# STM32-RF.net
KiCad netlist of a schematic drawn in EAGLE
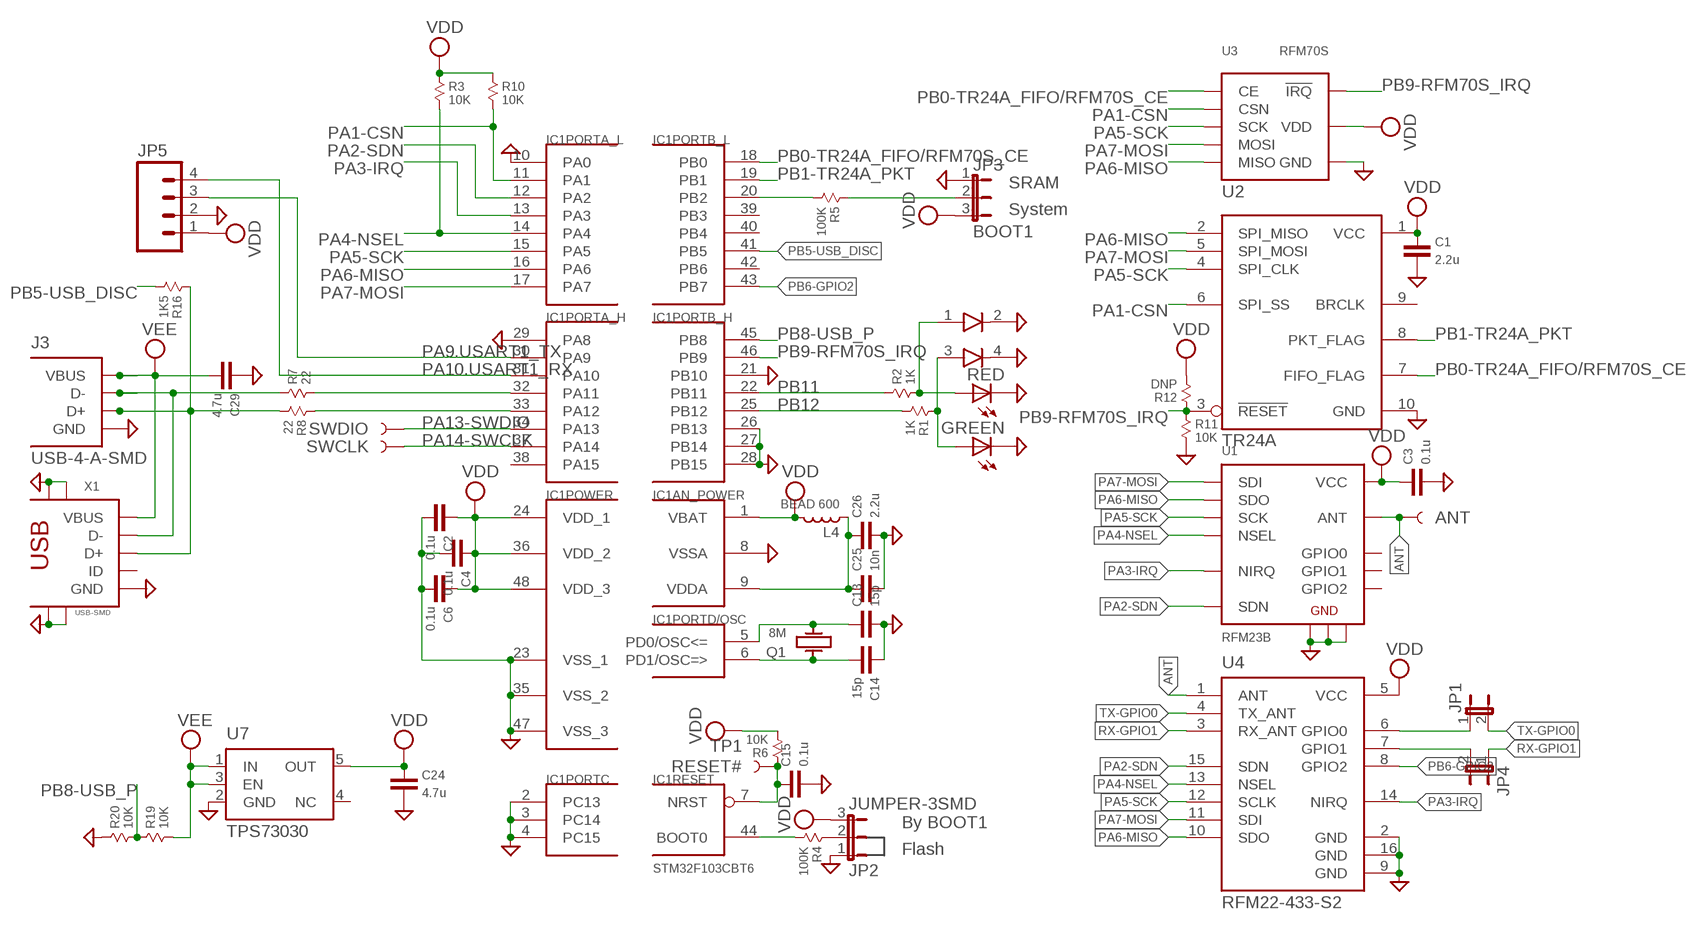
[diagram p0: schematic, sheet 1]

(export (version "E")
  (design (tool "Eeschema 10.0.6"))
  (components
    (comp (ref "ANT")
      (value "TEST-POINT1")
      (footprint "eagle-import:PAD.1X1")
      (libsource (lib "eagle-import") (part "TEST-POINT1"))
    )
    (comp (ref "C1")
      (value "2.2u")
      (footprint "eagle-import:0603")
      (libsource (lib "eagle-import") (part "CAP-0603"))
    )
    (comp (ref "C2")
      (value "0.1u")
      (footprint "eagle-import:0603")
      (libsource (lib "eagle-import") (part "CAP-0603"))
    )
    (comp (ref "C3")
      (value "0.1u")
      (footprint "eagle-import:0603")
      (libsource (lib "eagle-import") (part "CAP-0603"))
    )
    (comp (ref "C4")
      (value "0.1u")
      (footprint "eagle-import:0603")
      (libsource (lib "eagle-import") (part "CAP-0603"))
    )
    (comp (ref "C6")
      (value "0.1u")
      (footprint "eagle-import:0603")
      (libsource (lib "eagle-import") (part "CAP-0603"))
    )
    (comp (ref "C13")
      (value "15p")
      (footprint "eagle-import:0603")
      (libsource (lib "eagle-import") (part "CAP-0603"))
    )
    (comp (ref "C14")
      (value "15p")
      (footprint "eagle-import:0603")
      (libsource (lib "eagle-import") (part "CAP-0603"))
    )
    (comp (ref "C15")
      (value "0.1u")
      (footprint "eagle-import:0603")
      (libsource (lib "eagle-import") (part "CAP-0603"))
    )
    (comp (ref "C24")
      (value "4.7u")
      (footprint "eagle-import:0603")
      (libsource (lib "eagle-import") (part "CAP-0603"))
    )
    (comp (ref "C25")
      (value "10n")
      (footprint "eagle-import:0603")
      (libsource (lib "eagle-import") (part "CAP-0603"))
    )
    (comp (ref "C26")
      (value "2.2u")
      (footprint "eagle-import:0603")
      (libsource (lib "eagle-import") (part "CAP-0603"))
    )
    (comp (ref "C29")
      (value "4.7u")
      (footprint "eagle-import:0603")
      (libsource (lib "eagle-import") (part "CAP-0603"))
    )
    (comp (ref "GREEN")
      (value "LEDCHIPLED_0603")
      (footprint "eagle-import:CHIPLED_0603")
      (libsource (lib "eagle-import") (part "LEDCHIPLED_0603"))
    )
    (comp (ref "IC1")
      (value "STM32F103CBT6")
      (footprint "eagle-import:TQFP48")
      (libsource (lib "eagle-import") (part "STM32F10XCXT6"))
    )
    (comp (ref "J3")
      (value "USB-4-A-SMD")
      (footprint "eagle-import:USB-A-SMD")
      (libsource (lib "eagle-import") (part "USB-4-A-SMD"))
    )
    (comp (ref "JP1")
      (value "JUMPER-2SMD-NO")
      (footprint "eagle-import:SJ_2S-NO")
      (libsource (lib "eagle-import") (part "JUMPER-2SMD-NO"))
    )
    (comp (ref "JP2")
      (value "JUMPER-3SMD")
      (footprint "eagle-import:SJ_3")
      (libsource (lib "eagle-import") (part "JUMPER-3SMD"))
    )
    (comp (ref "JP3")
      (value "BOOT1")
      (footprint "eagle-import:SJ_3")
      (libsource (lib "eagle-import") (part "JUMPER-3SMD"))
    )
    (comp (ref "JP4")
      (value "JUMPER-2SMD-NO")
      (footprint "eagle-import:SJ_2S-NO")
      (libsource (lib "eagle-import") (part "JUMPER-2SMD-NO"))
    )
    (comp (ref "JP5")
      (value "M04PTH")
      (footprint "eagle-import:1X04")
      (libsource (lib "eagle-import") (part "M04PTH"))
    )
    (comp (ref "L4")
      (value "BEAD 600")
      (footprint "eagle-import:0603")
      (libsource (lib "eagle-import") (part "INDUCTOR-0603"))
    )
    (comp (ref "Q1")
      (value "8M")
      (footprint "eagle-import:KX-9A")
      (libsource (lib "eagle-import") (part "CRYSTAL-KX-9A"))
    )
    (comp (ref "R1")
      (value "1K")
      (footprint "eagle-import:0603")
      (libsource (lib "eagle-import") (part "RESISTOR-0603"))
    )
    (comp (ref "R2")
      (value "1K")
      (footprint "eagle-import:0603")
      (libsource (lib "eagle-import") (part "RESISTOR-0603"))
    )
    (comp (ref "R3")
      (value "10K")
      (footprint "eagle-import:0603")
      (libsource (lib "eagle-import") (part "RESISTOR-0603"))
    )
    (comp (ref "R4")
      (value "100K")
      (footprint "eagle-import:0603")
      (libsource (lib "eagle-import") (part "RESISTOR-0603"))
    )
    (comp (ref "R5")
      (value "100K")
      (footprint "eagle-import:0603")
      (libsource (lib "eagle-import") (part "RESISTOR-0603"))
    )
    (comp (ref "R6")
      (value "10K")
      (footprint "eagle-import:0603")
      (libsource (lib "eagle-import") (part "RESISTOR-0603"))
    )
    (comp (ref "R7")
      (value "22")
      (footprint "eagle-import:0603")
      (libsource (lib "eagle-import") (part "RESISTOR-0603"))
    )
    (comp (ref "R8")
      (value "22")
      (footprint "eagle-import:0603")
      (libsource (lib "eagle-import") (part "RESISTOR-0603"))
    )
    (comp (ref "R10")
      (value "10K")
      (footprint "eagle-import:0603")
      (libsource (lib "eagle-import") (part "RESISTOR-0603"))
    )
    (comp (ref "R11")
      (value "10K")
      (footprint "eagle-import:0603")
      (libsource (lib "eagle-import") (part "RESISTOR-0603"))
    )
    (comp (ref "R12")
      (value "DNP")
      (footprint "eagle-import:0603")
      (libsource (lib "eagle-import") (part "RESISTOR-0603"))
    )
    (comp (ref "R16")
      (value "1K5")
      (footprint "eagle-import:0603")
      (libsource (lib "eagle-import") (part "RESISTOR-0603"))
    )
    (comp (ref "R19")
      (value "10K")
      (footprint "eagle-import:0603")
      (libsource (lib "eagle-import") (part "RESISTOR-0603"))
    )
    (comp (ref "R20")
      (value "10K")
      (footprint "eagle-import:0603")
      (libsource (lib "eagle-import") (part "RESISTOR-0603"))
    )
    (comp (ref "RED")
      (value "LEDCHIPLED_0603")
      (footprint "eagle-import:CHIPLED_0603")
      (libsource (lib "eagle-import") (part "LEDCHIPLED_0603"))
    )
    (comp (ref "RESET#")
      (value "TP1")
      (footprint "eagle-import:PAD.1X1")
      (libsource (lib "eagle-import") (part "TEST-POINT1"))
    )
    (comp (ref "SWCLK")
      (value "TEST-POINT1")
      (footprint "eagle-import:PAD.1X1")
      (libsource (lib "eagle-import") (part "TEST-POINT1"))
    )
    (comp (ref "SWDIO")
      (value "TEST-POINT1")
      (footprint "eagle-import:PAD.1X1")
      (libsource (lib "eagle-import") (part "TEST-POINT1"))
    )
    (comp (ref "U$1")
      (value "LED-DUAL-0605")
      (footprint "eagle-import:LED-DUAL-0605")
      (libsource (lib "eagle-import") (part "LED-DUAL-0605"))
    )
    (comp (ref "U1")
      (value "RFM23B")
      (footprint "eagle-import:RFM2X")
      (libsource (lib "eagle-import") (part "RFM23B"))
    )
    (comp (ref "U2")
      (value "TR24A")
      (footprint "eagle-import:TR24A")
      (libsource (lib "eagle-import") (part "TR24A"))
    )
    (comp (ref "U3")
      (value "RFM70S")
      (footprint "eagle-import:RFM70S")
      (libsource (lib "eagle-import") (part "RFM70S"))
    )
    (comp (ref "U4")
      (value "RFM22-433-S2")
      (footprint "eagle-import:RFM2X")
      (libsource (lib "eagle-import") (part "RFM22-433-S2"))
    )
    (comp (ref "U7")
      (value "TPS73030")
      (footprint "eagle-import:SOT23-5")
      (libsource (lib "eagle-import") (part "TPS73033"))
    )
    (comp (ref "X1")
      (value "USB-SMD")
      (footprint "eagle-import:USB-MINIB")
      (libsource (lib "eagle-import") (part "USB-SMD"))
    )
  )
  (nets
    (net (code "1") (name "/PA1-CSN") (class "Default")
      (node (ref "IC1") (pin "11") (pinfunction "PA1_11") (pintype "bidirectional"))
      (node (ref "R10") (pin "2") (pinfunction "2_2") (pintype "passive"))
      (node (ref "U2") (pin "6") (pinfunction "SPI_SS_6") (pintype "input"))
      (node (ref "U3") (pin "CSN") (pinfunction "CSN_CSN") (pintype "input"))
    )
    (net (code "2") (name "/PA9.USART1_TX") (class "Default")
      (node (ref "IC1") (pin "30") (pinfunction "PA9_30") (pintype "bidirectional"))
      (node (ref "JP5") (pin "3") (pinfunction "3_3") (pintype "passive"))
    )
    (net (code "3") (name "/PA10.USART1_RX") (class "Default")
      (node (ref "IC1") (pin "31") (pinfunction "PA10_31") (pintype "bidirectional"))
      (node (ref "JP5") (pin "4") (pinfunction "4_4") (pintype "passive"))
    )
    (net (code "4") (name "/PA13-SWDIO") (class "Default")
      (node (ref "IC1") (pin "34") (pinfunction "PA13_34") (pintype "bidirectional"))
      (node (ref "SWDIO") (pin "P$1") (pinfunction "1_P$1") (pintype "bidirectional"))
    )
    (net (code "5") (name "/PA14-SWCLK") (class "Default")
      (node (ref "IC1") (pin "37") (pinfunction "PA14_37") (pintype "bidirectional"))
      (node (ref "SWCLK") (pin "P$1") (pinfunction "1_P$1") (pintype "bidirectional"))
    )
    (net (code "6") (name "/PB0-TR24A_FIFO{slash}RFM70S_CE") (class "Default")
      (node (ref "IC1") (pin "18") (pinfunction "PB0_18") (pintype "bidirectional"))
      (node (ref "U2") (pin "7") (pinfunction "FIFO_FLAG_7") (pintype "output"))
      (node (ref "U3") (pin "CE") (pinfunction "CE_CE") (pintype "input"))
    )
    (net (code "7") (name "/PB1-TR24A_PKT") (class "Default")
      (node (ref "IC1") (pin "19") (pinfunction "PB1_19") (pintype "bidirectional"))
      (node (ref "U2") (pin "8") (pinfunction "PKT_FLAG_8") (pintype "output"))
    )
    (net (code "8") (name "/PB8-USB_P") (class "Default")
      (node (ref "IC1") (pin "45") (pinfunction "PB8_45") (pintype "bidirectional"))
      (node (ref "R19") (pin "1") (pinfunction "1_1") (pintype "passive"))
      (node (ref "R20") (pin "2") (pinfunction "2_2") (pintype "passive"))
    )
    (net (code "9") (name "/PB9-RFM70S_IRQ") (class "Default")
      (node (ref "IC1") (pin "46") (pinfunction "PB9_46") (pintype "bidirectional"))
      (node (ref "R11") (pin "1") (pinfunction "1_1") (pintype "passive"))
      (node (ref "R12") (pin "1") (pinfunction "1_1") (pintype "passive"))
      (node (ref "U2") (pin "3") (pinfunction "~{RESET}_3") (pintype "input"))
      (node (ref "U3") (pin "IRQ") (pinfunction "~{IRQ}_IRQ") (pintype "output"))
    )
    (net (code "10") (name "/PB11") (class "Default")
      (node (ref "IC1") (pin "22") (pinfunction "PB11_22") (pintype "bidirectional"))
      (node (ref "R2") (pin "1") (pinfunction "1_1") (pintype "passive"))
    )
    (net (code "11") (name "/PB12") (class "Default")
      (node (ref "IC1") (pin "25") (pinfunction "PB12_25") (pintype "bidirectional"))
      (node (ref "R1") (pin "2") (pinfunction "2_2") (pintype "passive"))
    )
    (net (code "12") (name "ANT") (class "Default")
      (node (ref "ANT") (pin "P$1") (pinfunction "1_P$1") (pintype "bidirectional"))
      (node (ref "U1") (pin "1") (pinfunction "ANT_1") (pintype "passive"))
      (node (ref "U4") (pin "1") (pinfunction "ANT_1") (pintype "passive"))
    )
    (net (code "13") (name "GND") (class "Default")
      (node (ref "C1") (pin "1") (pinfunction "1_1") (pintype "passive"))
      (node (ref "C13") (pin "1") (pinfunction "1_1") (pintype "passive"))
      (node (ref "C14") (pin "2") (pinfunction "2_2") (pintype "passive"))
      (node (ref "C15") (pin "1") (pinfunction "1_1") (pintype "passive"))
      (node (ref "C2") (pin "1") (pinfunction "1_1") (pintype "passive"))
      (node (ref "C24") (pin "1") (pinfunction "1_1") (pintype "passive"))
      (node (ref "C25") (pin "1") (pinfunction "1_1") (pintype "passive"))
      (node (ref "C26") (pin "1") (pinfunction "1_1") (pintype "passive"))
      (node (ref "C29") (pin "2") (pinfunction "2_2") (pintype "passive"))
      (node (ref "C3") (pin "1") (pinfunction "1_1") (pintype "passive"))
      (node (ref "C4") (pin "1") (pinfunction "1_1") (pintype "passive"))
      (node (ref "C6") (pin "1") (pinfunction "1_1") (pintype "passive"))
      (node (ref "GREEN") (pin "C") (pinfunction "C_C") (pintype "passive"))
      (node (ref "IC1") (pin "10") (pinfunction "PA0_10") (pintype "bidirectional"))
      (node (ref "IC1") (pin "2") (pinfunction "PC13_2") (pintype "bidirectional"))
      (node (ref "IC1") (pin "21") (pinfunction "PB10_21") (pintype "bidirectional"))
      (node (ref "IC1") (pin "23") (pinfunction "VSS_1_23") (pintype "power_in"))
      (node (ref "IC1") (pin "26") (pinfunction "PB13_26") (pintype "bidirectional"))
      (node (ref "IC1") (pin "27") (pinfunction "PB14_27") (pintype "bidirectional"))
      (node (ref "IC1") (pin "28") (pinfunction "PB15_28") (pintype "bidirectional"))
      (node (ref "IC1") (pin "29") (pinfunction "PA8_29") (pintype "bidirectional"))
      (node (ref "IC1") (pin "3") (pinfunction "PC14_3") (pintype "bidirectional"))
      (node (ref "IC1") (pin "35") (pinfunction "VSS_2_35") (pintype "power_in"))
      (node (ref "IC1") (pin "4") (pinfunction "PC15_4") (pintype "bidirectional"))
      (node (ref "IC1") (pin "47") (pinfunction "VSS_3_47") (pintype "power_in"))
      (node (ref "IC1") (pin "8") (pinfunction "VSSA_8") (pintype "power_in"))
      (node (ref "J3") (pin "GND") (pinfunction "GND_GND") (pintype "power_in"))
      (node (ref "JP2") (pin "1") (pinfunction "1_1") (pintype "passive"))
      (node (ref "JP3") (pin "1") (pinfunction "1_1") (pintype "passive"))
      (node (ref "JP5") (pin "2") (pinfunction "2_2") (pintype "passive"))
      (node (ref "R11") (pin "2") (pinfunction "2_2") (pintype "passive"))
      (node (ref "R20") (pin "1") (pinfunction "1_1") (pintype "passive"))
      (node (ref "RED") (pin "C") (pinfunction "C_C") (pintype "passive"))
      (node (ref "U$1") (pin "2") (pinfunction "2_2") (pintype "passive"))
      (node (ref "U$1") (pin "4") (pinfunction "4_4") (pintype "passive"))
      (node (ref "U1") (pin "16") (pinfunction "GND_16") (pintype "power_in"))
      (node (ref "U1") (pin "2") (pinfunction "GND_2") (pintype "power_in"))
      (node (ref "U1") (pin "9") (pinfunction "GND_9") (pintype "power_in"))
      (node (ref "U2") (pin "10") (pinfunction "GND_10") (pintype "power_in"))
      (node (ref "U3") (pin "GND") (pinfunction "GND_GND") (pintype "power_in"))
      (node (ref "U4") (pin "16") (pinfunction "GND_16") (pintype "power_in"))
      (node (ref "U4") (pin "2") (pinfunction "GND_2") (pintype "power_in"))
      (node (ref "U4") (pin "9") (pinfunction "GND_9") (pintype "power_in"))
      (node (ref "U7") (pin "2") (pinfunction "GND_2") (pintype "power_in"))
      (node (ref "X1") (pin "GND") (pinfunction "GND_GND") (pintype "power_in"))
      (node (ref "X1") (pin "GND@1") (pinfunction "GND_GND@1") (pintype "power_in"))
      (node (ref "X1") (pin "GND@2") (pinfunction "GND_GND@2") (pintype "power_in"))
      (node (ref "X1") (pin "GND@3") (pinfunction "GND_GND@3") (pintype "power_in"))
      (node (ref "X1") (pin "GND@4") (pinfunction "GND_GND@4") (pintype "power_in"))
    )
    (net (code "14") (name "Net-(GREEN-PadA)") (class "Default")
      (node (ref "GREEN") (pin "A") (pinfunction "A_A") (pintype "passive"))
      (node (ref "R1") (pin "1") (pinfunction "1_1") (pintype "passive"))
      (node (ref "U$1") (pin "3") (pinfunction "3_3") (pintype "passive"))
    )
    (net (code "15") (name "Net-(IC1A-VDDA)") (class "Default")
      (node (ref "C25") (pin "2") (pinfunction "2_2") (pintype "passive"))
      (node (ref "C26") (pin "2") (pinfunction "2_2") (pintype "passive"))
      (node (ref "IC1") (pin "9") (pinfunction "VDDA_9") (pintype "power_in"))
      (node (ref "L4") (pin "1") (pinfunction "1_1") (pintype "passive"))
    )
    (net (code "16") (name "Net-(IC1B-PA11)") (class "Default")
      (node (ref "IC1") (pin "32") (pinfunction "PA11_32") (pintype "bidirectional"))
      (node (ref "R7") (pin "2") (pinfunction "2_2") (pintype "passive"))
    )
    (net (code "17") (name "Net-(IC1B-PA12)") (class "Default")
      (node (ref "IC1") (pin "33") (pinfunction "PA12_33") (pintype "bidirectional"))
      (node (ref "R8") (pin "1") (pinfunction "1_1") (pintype "passive"))
    )
    (net (code "18") (name "Net-(IC1E-PB2)") (class "Default")
      (node (ref "IC1") (pin "20") (pinfunction "PB2_20") (pintype "bidirectional"))
      (node (ref "R5") (pin "2") (pinfunction "2_2") (pintype "passive"))
    )
    (net (code "19") (name "Net-(IC1G-PD0{slash}OSC<=)") (class "Default")
      (node (ref "C13") (pin "2") (pinfunction "2_2") (pintype "passive"))
      (node (ref "IC1") (pin "5") (pinfunction "PD0/OSC<=_5") (pintype "bidirectional"))
      (node (ref "Q1") (pin "3") (pinfunction "2_3") (pintype "passive"))
    )
    (net (code "20") (name "Net-(IC1G-PD1{slash}OSC=>)") (class "Default")
      (node (ref "C14") (pin "1") (pinfunction "1_1") (pintype "passive"))
      (node (ref "IC1") (pin "6") (pinfunction "PD1/OSC=>_6") (pintype "bidirectional"))
      (node (ref "Q1") (pin "1") (pinfunction "1_1") (pintype "passive"))
    )
    (net (code "21") (name "Net-(IC1I-BOOT0)") (class "Default")
      (node (ref "IC1") (pin "44") (pinfunction "BOOT0_44") (pintype "input"))
      (node (ref "R4") (pin "2") (pinfunction "2_2") (pintype "passive"))
    )
    (net (code "22") (name "Net-(IC1I-NRST)") (class "Default")
      (node (ref "C15") (pin "2") (pinfunction "2_2") (pintype "passive"))
      (node (ref "IC1") (pin "7") (pinfunction "NRST_7") (pintype "input"))
      (node (ref "R6") (pin "1") (pinfunction "1_1") (pintype "passive"))
      (node (ref "RESET#") (pin "P$1") (pinfunction "1_P$1") (pintype "bidirectional"))
    )
    (net (code "23") (name "Net-(J3-PadD+)") (class "Default")
      (node (ref "J3") (pin "D+") (pinfunction "D+_D+") (pintype "bidirectional"))
      (node (ref "R16") (pin "1") (pinfunction "1_1") (pintype "passive"))
      (node (ref "R8") (pin "2") (pinfunction "2_2") (pintype "passive"))
      (node (ref "X1") (pin "D+") (pinfunction "D+_D+") (pintype "bidirectional"))
    )
    (net (code "24") (name "Net-(J3-PadD-)") (class "Default")
      (node (ref "J3") (pin "D-") (pinfunction "D-_D-") (pintype "bidirectional"))
      (node (ref "R7") (pin "1") (pinfunction "1_1") (pintype "passive"))
      (node (ref "X1") (pin "D-") (pinfunction "D-_D-") (pintype "bidirectional"))
    )
    (net (code "25") (name "Net-(JP2-Pad2)") (class "Default")
      (node (ref "JP2") (pin "2") (pinfunction "2_2") (pintype "passive"))
      (node (ref "R4") (pin "1") (pinfunction "1_1") (pintype "passive"))
    )
    (net (code "26") (name "Net-(JP3-Pad2)") (class "Default")
      (node (ref "JP3") (pin "2") (pinfunction "2_2") (pintype "passive"))
      (node (ref "R5") (pin "1") (pinfunction "1_1") (pintype "passive"))
    )
    (net (code "27") (name "Net-(R2-Pad2)") (class "Default")
      (node (ref "R2") (pin "2") (pinfunction "2_2") (pintype "passive"))
      (node (ref "RED") (pin "A") (pinfunction "A_A") (pintype "passive"))
      (node (ref "U$1") (pin "1") (pinfunction "1_1") (pintype "passive"))
    )
    (net (code "28") (name "Net-(U4-GPIO0)") (class "Default")
      (node (ref "JP1") (pin "1") (pinfunction "1_1") (pintype "passive"))
      (node (ref "U4") (pin "6") (pinfunction "GPIO0_6") (pintype "bidirectional"))
    )
    (net (code "29") (name "Net-(U4-GPIO1)") (class "Default")
      (node (ref "JP4") (pin "2") (pinfunction "2_2") (pintype "passive"))
      (node (ref "U4") (pin "7") (pinfunction "GPIO1_7") (pintype "bidirectional"))
    )
    (net (code "30") (name "PA2-SDN") (class "Default")
      (node (ref "IC1") (pin "12") (pinfunction "PA2_12") (pintype "bidirectional"))
      (node (ref "U1") (pin "15") (pinfunction "SDN_15") (pintype "input"))
      (node (ref "U4") (pin "15") (pinfunction "SDN_15") (pintype "input"))
    )
    (net (code "31") (name "PA3-IRQ") (class "Default")
      (node (ref "IC1") (pin "13") (pinfunction "PA3_13") (pintype "bidirectional"))
      (node (ref "U1") (pin "14") (pinfunction "NIRQ_14") (pintype "bidirectional"))
      (node (ref "U4") (pin "14") (pinfunction "NIRQ_14") (pintype "input"))
    )
    (net (code "32") (name "PA4-NSEL") (class "Default")
      (node (ref "IC1") (pin "14") (pinfunction "PA4_14") (pintype "bidirectional"))
      (node (ref "R3") (pin "2") (pinfunction "2_2") (pintype "passive"))
      (node (ref "U1") (pin "13") (pinfunction "NSEL_13") (pintype "input"))
      (node (ref "U4") (pin "13") (pinfunction "NSEL_13") (pintype "input"))
    )
    (net (code "33") (name "PA5-SCK") (class "Default")
      (node (ref "IC1") (pin "15") (pinfunction "PA5_15") (pintype "bidirectional"))
      (node (ref "U1") (pin "12") (pinfunction "SCK_12") (pintype "input"))
      (node (ref "U2") (pin "4") (pinfunction "SPI_CLK_4") (pintype "input"))
      (node (ref "U3") (pin "SCK") (pinfunction "SCK_SCK") (pintype "input"))
      (node (ref "U4") (pin "12") (pinfunction "SCLK_12") (pintype "input"))
    )
    (net (code "34") (name "PA6-MISO") (class "Default")
      (node (ref "IC1") (pin "16") (pinfunction "PA6_16") (pintype "bidirectional"))
      (node (ref "U1") (pin "10") (pinfunction "SDO_10") (pintype "bidirectional"))
      (node (ref "U2") (pin "2") (pinfunction "SPI_MISO_2") (pintype "bidirectional"))
      (node (ref "U3") (pin "MISO") (pinfunction "MISO_MISO") (pintype "tri_state"))
      (node (ref "U4") (pin "10") (pinfunction "SDO_10") (pintype "output"))
    )
    (net (code "35") (name "PA7-MOSI") (class "Default")
      (node (ref "IC1") (pin "17") (pinfunction "PA7_17") (pintype "bidirectional"))
      (node (ref "U1") (pin "11") (pinfunction "SDI_11") (pintype "input"))
      (node (ref "U2") (pin "5") (pinfunction "SPI_MOSI_5") (pintype "input"))
      (node (ref "U3") (pin "MOSI") (pinfunction "MOSI_MOSI") (pintype "input"))
      (node (ref "U4") (pin "11") (pinfunction "SDI_11") (pintype "input"))
    )
    (net (code "36") (name "PB5-USB_DISC") (class "Default")
      (node (ref "IC1") (pin "41") (pinfunction "PB5_41") (pintype "bidirectional"))
      (node (ref "R16") (pin "2") (pinfunction "2_2") (pintype "passive"))
    )
    (net (code "37") (name "PB6-GPIO2") (class "Default")
      (node (ref "IC1") (pin "43") (pinfunction "PB7_43") (pintype "bidirectional"))
      (node (ref "U4") (pin "8") (pinfunction "GPIO2_8") (pintype "bidirectional"))
    )
    (net (code "38") (name "RX-GPIO1") (class "Default")
      (node (ref "JP4") (pin "1") (pinfunction "1_1") (pintype "passive"))
      (node (ref "U4") (pin "3") (pinfunction "RX_ANT_3") (pintype "input"))
    )
    (net (code "39") (name "TX-GPIO0") (class "Default")
      (node (ref "JP1") (pin "2") (pinfunction "2_2") (pintype "passive"))
      (node (ref "U4") (pin "4") (pinfunction "TX_ANT_4") (pintype "input"))
    )
    (net (code "40") (name "VDD") (class "Default")
      (node (ref "C1") (pin "2") (pinfunction "2_2") (pintype "passive"))
      (node (ref "C2") (pin "2") (pinfunction "2_2") (pintype "passive"))
      (node (ref "C24") (pin "2") (pinfunction "2_2") (pintype "passive"))
      (node (ref "C3") (pin "2") (pinfunction "2_2") (pintype "passive"))
      (node (ref "C4") (pin "2") (pinfunction "2_2") (pintype "passive"))
      (node (ref "C6") (pin "2") (pinfunction "2_2") (pintype "passive"))
      (node (ref "IC1") (pin "1") (pinfunction "VBAT_1") (pintype "power_in"))
      (node (ref "IC1") (pin "24") (pinfunction "VDD_1_24") (pintype "power_in"))
      (node (ref "IC1") (pin "36") (pinfunction "VDD_2_36") (pintype "power_in"))
      (node (ref "IC1") (pin "48") (pinfunction "VDD_3_48") (pintype "power_in"))
      (node (ref "JP2") (pin "3") (pinfunction "3_3") (pintype "passive"))
      (node (ref "JP3") (pin "3") (pinfunction "3_3") (pintype "passive"))
      (node (ref "JP5") (pin "1") (pinfunction "1_1") (pintype "passive"))
      (node (ref "L4") (pin "2") (pinfunction "2_2") (pintype "passive"))
      (node (ref "R10") (pin "1") (pinfunction "1_1") (pintype "passive"))
      (node (ref "R12") (pin "2") (pinfunction "2_2") (pintype "passive"))
      (node (ref "R3") (pin "1") (pinfunction "1_1") (pintype "passive"))
      (node (ref "R6") (pin "2") (pinfunction "2_2") (pintype "passive"))
      (node (ref "U1") (pin "5") (pinfunction "VCC_5") (pintype "power_in"))
      (node (ref "U2") (pin "1") (pinfunction "VCC_1") (pintype "bidirectional"))
      (node (ref "U3") (pin "VDD") (pinfunction "VDD_VDD") (pintype "power_in"))
      (node (ref "U4") (pin "5") (pinfunction "VCC_5") (pintype "power_in"))
      (node (ref "U7") (pin "5") (pinfunction "OUT_5") (pintype "passive"))
    )
    (net (code "41") (name "VEE") (class "Default")
      (node (ref "C29") (pin "1") (pinfunction "1_1") (pintype "passive"))
      (node (ref "J3") (pin "VUSB") (pinfunction "VBUS_VUSB") (pintype "passive"))
      (node (ref "R19") (pin "2") (pinfunction "2_2") (pintype "passive"))
      (node (ref "U7") (pin "1") (pinfunction "IN_1") (pintype "passive"))
      (node (ref "U7") (pin "3") (pinfunction "EN_3") (pintype "input"))
      (node (ref "X1") (pin "VBUS") (pinfunction "VBUS_VBUS") (pintype "passive"))
    )
    (net (code "42") (name "unconnected-(IC1B-PA15-Pad38)") (class "Default")
      (node (ref "IC1") (pin "38") (pinfunction "PA15_38") (pintype "bidirectional"))
    )
    (net (code "43") (name "unconnected-(IC1E-PB3-Pad39)") (class "Default")
      (node (ref "IC1") (pin "39") (pinfunction "PB3_39") (pintype "bidirectional"))
    )
    (net (code "44") (name "unconnected-(IC1E-PB4-Pad40)") (class "Default")
      (node (ref "IC1") (pin "40") (pinfunction "PB4_40") (pintype "bidirectional"))
    )
    (net (code "45") (name "unconnected-(IC1E-PB6-Pad42)") (class "Default")
      (node (ref "IC1") (pin "42") (pinfunction "PB6_42") (pintype "bidirectional"))
    )
    (net (code "46") (name "unconnected-(U1-GPIO0-Pad6)") (class "Default")
      (node (ref "U1") (pin "6") (pinfunction "GPIO0_6") (pintype "bidirectional"))
    )
    (net (code "47") (name "unconnected-(U1-GPIO1-Pad7)") (class "Default")
      (node (ref "U1") (pin "7") (pinfunction "GPIO1_7") (pintype "bidirectional"))
    )
    (net (code "48") (name "unconnected-(U1-GPIO2-Pad8)") (class "Default")
      (node (ref "U1") (pin "8") (pinfunction "GPIO2_8") (pintype "bidirectional"))
    )
    (net (code "49") (name "unconnected-(U1-NC-Pad3)") (class "Default")
      (node (ref "U1") (pin "3") (pinfunction "NC_3") (pintype "no_connect"))
    )
    (net (code "50") (name "unconnected-(U1-NC-Pad4)") (class "Default")
      (node (ref "U1") (pin "4") (pinfunction "NC_4") (pintype "no_connect"))
    )
    (net (code "51") (name "unconnected-(U2-BRCLK-Pad9)") (class "Default")
      (node (ref "U2") (pin "9") (pinfunction "BRCLK_9") (pintype "output"))
    )
    (net (code "52") (name "unconnected-(U7-NC-Pad4)") (class "Default")
      (node (ref "U7") (pin "4") (pinfunction "NC_4") (pintype "no_connect"))
    )
    (net (code "53") (name "unconnected-(X1-PadID)") (class "Default")
      (node (ref "X1") (pin "ID") (pinfunction "ID_ID") (pintype "bidirectional"))
    )
  )
)
